# MCU.net
KiCad netlist of a schematic drawn in Altium Designer
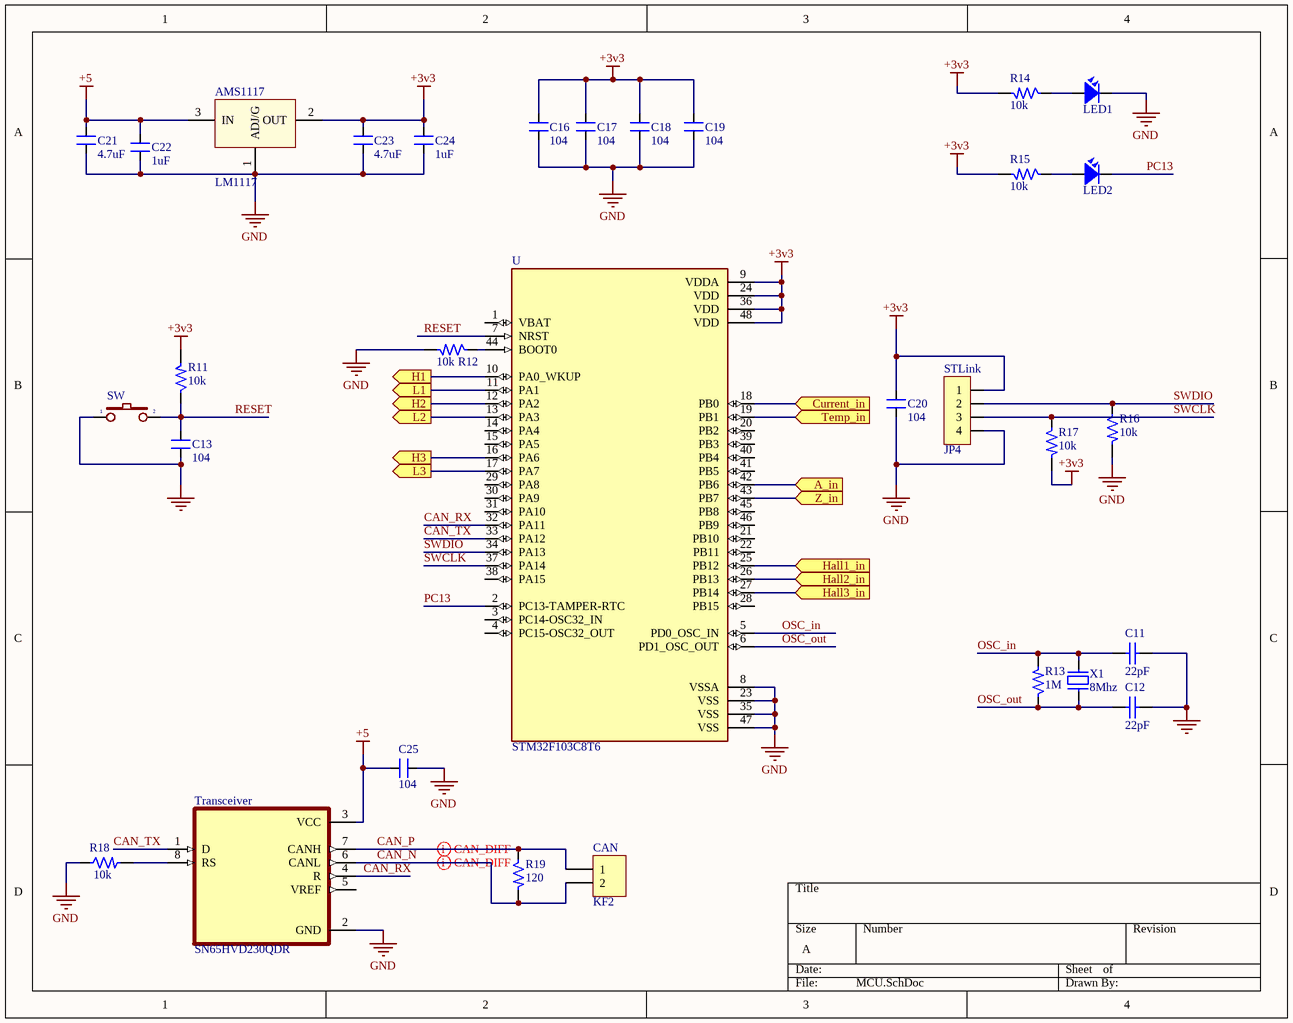
[diagram p0: MCU.SchDoc]

(export (version "E")
  (design (tool "Eeschema 10.0.6"))
  (components
    (comp (ref "AMS1117")
      (value "LM1117")
      (footprint "SOT223-4N")
      (description "Available in 1.8V, 2.5V, 2.85V, 3.3V, 5V, and  Adjustable Versions")
      (libsource (lib "echipkool-com-library") (part "LM1117"))
    )
    (comp (ref "C11")
      (value "22pF")
      (footprint "CAP FILM 0603_1608")
      (description "Capacitor")
      (fields (field (name "PUBLISHER") "Altium Limited"))
      (libsource (lib "My Library") (part "CapSMD"))
    )
    (comp (ref "C12")
      (value "22pF")
      (footprint "CAP FILM 0603_1608")
      (description "Capacitor")
      (fields (field (name "PUBLISHER") "Altium Limited"))
      (libsource (lib "My Library") (part "CapSMD"))
    )
    (comp (ref "C13")
      (value "104")
      (footprint "CAP FILM 0603_1608")
      (fields (field (name "DESIGNED BY") "VanDungEvn"))
      (libsource (lib "echipkool-com-library") (part "CN"))
    )
    (comp (ref "C16")
      (value "104")
      (footprint "CAP FILM 0603_1608")
      (fields (field (name "DESIGNED BY") "VanDungEvn"))
      (libsource (lib "echipkool-com-library") (part "CN"))
    )
    (comp (ref "C17")
      (value "104")
      (footprint "CAP FILM 0603_1608")
      (fields (field (name "DESIGNED BY") "VanDungEvn"))
      (libsource (lib "echipkool-com-library") (part "CN"))
    )
    (comp (ref "C18")
      (value "104")
      (footprint "CAP FILM 0603_1608")
      (fields (field (name "DESIGNED BY") "VanDungEvn"))
      (libsource (lib "echipkool-com-library") (part "CN"))
    )
    (comp (ref "C19")
      (value "104")
      (footprint "CAP FILM 0603_1608")
      (fields (field (name "DESIGNED BY") "VanDungEvn"))
      (libsource (lib "echipkool-com-library") (part "CN"))
    )
    (comp (ref "C20")
      (value "104")
      (footprint "CAP FILM 0603_1608")
      (fields (field (name "DESIGNED BY") "VanDungEvn"))
      (libsource (lib "echipkool-com-library") (part "CN"))
    )
    (comp (ref "C21")
      (value "4.7uF")
      (footprint "CAP FILM 0603_1608")
      (fields (field (name "DESIGNED BY") "VanDungEvn"))
      (libsource (lib "echipkool-com-library") (part "CN"))
    )
    (comp (ref "C22")
      (value "1uF")
      (footprint "CAP FILM 0603_1608")
      (fields (field (name "DESIGNED BY") "VanDungEvn"))
      (libsource (lib "echipkool-com-library") (part "CN"))
    )
    (comp (ref "C23")
      (value "4.7uF")
      (footprint "CAP FILM 0603_1608")
      (fields (field (name "DESIGNED BY") "VanDungEvn"))
      (libsource (lib "echipkool-com-library") (part "CN"))
    )
    (comp (ref "C24")
      (value "1uF")
      (footprint "CAP FILM 0603_1608")
      (fields (field (name "DESIGNED BY") "VanDungEvn"))
      (libsource (lib "echipkool-com-library") (part "CN"))
    )
    (comp (ref "C25")
      (value "104")
      (footprint "CAP FILM 0603_1608")
      (fields (field (name "DESIGNED BY") "VanDungEvn"))
      (libsource (lib "echipkool-com-library") (part "CN"))
    )
    (comp (ref "CAN")
      (value "KF2")
      (footprint "KF2-5.08")
      (fields
        (field (name "MANUFACTURER") "Würth Elektronik eiSos GmbH")
        (field (name "PARTNO") "691103110002")
        (field (name "CREATED BY") "Karrer Zheng")
      )
      (libsource (lib "LIBRARYALT") (part "KF2"))
    )
    (comp (ref "LED1")
      (value "LED SMD")
      (footprint "LED 0603_1608 GREEN")
      (libsource (lib "echipkool-com-library") (part "LED-SMD-0805"))
    )
    (comp (ref "LED2")
      (value "LED SMD")
      (footprint "LED 0603_1608 GREEN")
      (libsource (lib "echipkool-com-library") (part "LED-SMD-0805"))
    )
    (comp (ref "R11")
      (value "10k")
      (footprint "RES 0603_1608")
      (description "Resistor 1/4W")
      (libsource (lib "echipkool-com-library") (part "R"))
    )
    (comp (ref "R12")
      (value "10k")
      (footprint "RES 0603_1608")
      (description "Resistor 1/4W")
      (libsource (lib "echipkool-com-library") (part "R"))
    )
    (comp (ref "R13")
      (value "1M")
      (footprint "RES 0603_1608")
      (description "Resistor 1/4W")
      (libsource (lib "echipkool-com-library") (part "R"))
    )
    (comp (ref "R14")
      (value "10k")
      (footprint "RES 0603_1608")
      (description "Resistor 1/4W")
      (libsource (lib "echipkool-com-library") (part "R"))
    )
    (comp (ref "R15")
      (value "10k")
      (footprint "RES 0603_1608")
      (description "Resistor 1/4W")
      (libsource (lib "echipkool-com-library") (part "R"))
    )
    (comp (ref "R16")
      (value "10k")
      (footprint "RES 0603_1608")
      (description "Resistor 1/4W")
      (libsource (lib "echipkool-com-library") (part "R"))
    )
    (comp (ref "R17")
      (value "10k")
      (footprint "RES 0603_1608")
      (description "Resistor 1/4W")
      (libsource (lib "echipkool-com-library") (part "R"))
    )
    (comp (ref "R18")
      (value "10k")
      (footprint "RES 0603_1608")
      (description "Resistor 1/4W")
      (libsource (lib "echipkool-com-library") (part "R"))
    )
    (comp (ref "R19")
      (value "120")
      (footprint "RES 0603_1608")
      (description "Resistor 1/4W")
      (libsource (lib "echipkool-com-library") (part "R"))
    )
    (comp (ref "STLink")
      (value "JP4")
      (footprint "JP4-D1C")
      (description "WR-PHD 2.54 mm Angled Socket Header")
      (fields
        (field (name "MANUFACTURER") "Würth Elektronik eiSos GmbH")
        (field (name "PARTNO") "613004143121")
        (field (name "CREATED BY") "Karrer Zheng")
      )
      (libsource (lib "LIBRARYALT") (part "JP4"))
    )
    (comp (ref "SW")
      (value "~")
      (footprint "SW1-SMD")
      (description "Switch button 2 pin")
      (libsource (lib "LIBRARYALT") (part "SW2"))
    )
    (comp (ref "Transceiver")
      (value "SN65HVD230QDR")
      (footprint "SOIC127P599X175-8N")
      (description "3.3-V CAN Transceiver with Standby Mode 8-SOIC -40 to 125")
      (fields (field (name "MF") "Texas Instruments"))
      (libsource (lib "SN65HVD230QDR") (part "SN65HVD230QDR"))
    )
    (comp (ref "U")
      (value "STM32F103C8T6")
      (footprint "QFP50P900X900X160-48N")
      (description "ARMÂ® CortexÂ®-M3 STM32F1 Microcontroller IC 32-Bit 72MHz 64KB _64K x 8_ FLASH")
      (fields (field (name "MF") "STMicroelectronics"))
      (libsource (lib "STM32F103C8T6") (part "STM32F103C8T6"))
    )
    (comp (ref "X1")
      (value "8Mhz")
      (footprint "XTAL-RU49/4")
      (description "Crystal, 32.768 KHz, -40 to 85 degC, 3.2 x 1.5 x 0.9 mm SMD")
      (libsource (lib "LIBRARYALT") (part "XT2"))
    )
  )
  (nets
    (net (code "1") (name "+3v3") (class "Default")
      (node (ref "AMS1117") (pin "2") (pinfunction "OUT_2") (pintype "passive"))
      (node (ref "C16") (pin "1") (pinfunction "1_1") (pintype "passive"))
      (node (ref "C17") (pin "1") (pinfunction "1_1") (pintype "passive"))
      (node (ref "C18") (pin "1") (pinfunction "1_1") (pintype "passive"))
      (node (ref "C19") (pin "1") (pinfunction "1_1") (pintype "passive"))
      (node (ref "C20") (pin "1") (pinfunction "1_1") (pintype "passive"))
      (node (ref "C23") (pin "1") (pinfunction "1_1") (pintype "passive"))
      (node (ref "C24") (pin "1") (pinfunction "1_1") (pintype "passive"))
      (node (ref "R11") (pin "2") (pinfunction "2_2") (pintype "passive"))
      (node (ref "R14") (pin "2") (pinfunction "2_2") (pintype "passive"))
      (node (ref "R15") (pin "2") (pinfunction "2_2") (pintype "passive"))
      (node (ref "R17") (pin "2") (pinfunction "2_2") (pintype "passive"))
      (node (ref "STLink") (pin "1") (pinfunction "1_1") (pintype "passive"))
      (node (ref "U") (pin "24") (pinfunction "VDD_24") (pintype "power_in"))
      (node (ref "U") (pin "36") (pinfunction "VDD_36") (pintype "power_in"))
      (node (ref "U") (pin "48") (pinfunction "VDD_48") (pintype "power_in"))
      (node (ref "U") (pin "9") (pinfunction "VDDA_9") (pintype "power_in"))
    )
    (net (code "2") (name "+5") (class "Default")
      (node (ref "AMS1117") (pin "3") (pinfunction "IN_3") (pintype "passive"))
      (node (ref "C21") (pin "1") (pinfunction "1_1") (pintype "passive"))
      (node (ref "C22") (pin "1") (pinfunction "1_1") (pintype "passive"))
      (node (ref "C25") (pin "1") (pinfunction "1_1") (pintype "passive"))
      (node (ref "Transceiver") (pin "3") (pinfunction "VCC_3") (pintype "power_in"))
    )
    (net (code "3") (name "/A_in") (class "Default")
      (node (ref "U") (pin "42") (pinfunction "PB6_42") (pintype "bidirectional"))
    )
    (net (code "4") (name "/CAN_N") (class "Default")
      (node (ref "CAN") (pin "2") (pinfunction "2_2") (pintype "passive"))
      (node (ref "R19") (pin "2") (pinfunction "2_2") (pintype "passive"))
      (node (ref "Transceiver") (pin "6") (pinfunction "CANL_6") (pintype "output"))
    )
    (net (code "5") (name "/CAN_P") (class "Default")
      (node (ref "CAN") (pin "1") (pinfunction "1_1") (pintype "passive"))
      (node (ref "R19") (pin "1") (pinfunction "1_1") (pintype "passive"))
      (node (ref "Transceiver") (pin "7") (pinfunction "CANH_7") (pintype "output"))
    )
    (net (code "6") (name "/CAN_RX") (class "Default")
      (node (ref "Transceiver") (pin "4") (pinfunction "R_4") (pintype "output"))
      (node (ref "U") (pin "32") (pinfunction "PA11_32") (pintype "bidirectional"))
    )
    (net (code "7") (name "/CAN_TX") (class "Default")
      (node (ref "Transceiver") (pin "1") (pinfunction "D_1") (pintype "input"))
      (node (ref "U") (pin "33") (pinfunction "PA12_33") (pintype "bidirectional"))
    )
    (net (code "8") (name "/Current_in") (class "Default")
      (node (ref "U") (pin "18") (pinfunction "PB0_18") (pintype "bidirectional"))
    )
    (net (code "9") (name "/H1") (class "Default")
      (node (ref "U") (pin "10") (pinfunction "PA0_WKUP_10") (pintype "bidirectional"))
    )
    (net (code "10") (name "/H2") (class "Default")
      (node (ref "U") (pin "12") (pinfunction "PA2_12") (pintype "bidirectional"))
    )
    (net (code "11") (name "/H3") (class "Default")
      (node (ref "U") (pin "16") (pinfunction "PA6_16") (pintype "bidirectional"))
    )
    (net (code "12") (name "/Hall1_in") (class "Default")
      (node (ref "U") (pin "25") (pinfunction "PB12_25") (pintype "bidirectional"))
    )
    (net (code "13") (name "/Hall2_in") (class "Default")
      (node (ref "U") (pin "26") (pinfunction "PB13_26") (pintype "bidirectional"))
    )
    (net (code "14") (name "/Hall3_in") (class "Default")
      (node (ref "U") (pin "27") (pinfunction "PB14_27") (pintype "bidirectional"))
    )
    (net (code "15") (name "/L1") (class "Default")
      (node (ref "U") (pin "11") (pinfunction "PA1_11") (pintype "bidirectional"))
    )
    (net (code "16") (name "/L2") (class "Default")
      (node (ref "U") (pin "13") (pinfunction "PA3_13") (pintype "bidirectional"))
    )
    (net (code "17") (name "/L3") (class "Default")
      (node (ref "U") (pin "17") (pinfunction "PA7_17") (pintype "bidirectional"))
    )
    (net (code "18") (name "/OSC_in") (class "Default")
      (node (ref "C11") (pin "2") (pinfunction "2_2") (pintype "passive"))
      (node (ref "R13") (pin "2") (pinfunction "2_2") (pintype "passive"))
      (node (ref "U") (pin "5") (pinfunction "PD0_OSC_IN_5") (pintype "bidirectional"))
      (node (ref "X1") (pin "2") (pinfunction "2_2") (pintype "passive"))
    )
    (net (code "19") (name "/OSC_out") (class "Default")
      (node (ref "C12") (pin "2") (pinfunction "2_2") (pintype "passive"))
      (node (ref "R13") (pin "1") (pinfunction "1_1") (pintype "passive"))
      (node (ref "U") (pin "6") (pinfunction "PD1_OSC_OUT_6") (pintype "bidirectional"))
      (node (ref "X1") (pin "1") (pinfunction "1_1") (pintype "passive"))
    )
    (net (code "20") (name "/PC13") (class "Default")
      (node (ref "LED2") (pin "2") (pinfunction "2_2") (pintype "passive"))
      (node (ref "U") (pin "2") (pinfunction "PC13-TAMPER-RTC_2") (pintype "bidirectional"))
    )
    (net (code "21") (name "/RESET") (class "Default")
      (node (ref "C13") (pin "1") (pinfunction "1_1") (pintype "passive"))
      (node (ref "R11") (pin "1") (pinfunction "1_1") (pintype "passive"))
      (node (ref "SW") (pin "2") (pinfunction "2_2") (pintype "passive"))
      (node (ref "U") (pin "7") (pinfunction "NRST_7") (pintype "input"))
    )
    (net (code "22") (name "/SWCLK") (class "Default")
      (node (ref "R17") (pin "1") (pinfunction "1_1") (pintype "passive"))
      (node (ref "STLink") (pin "3") (pinfunction "3_3") (pintype "passive"))
      (node (ref "U") (pin "37") (pinfunction "PA14_37") (pintype "bidirectional"))
    )
    (net (code "23") (name "/SWDIO") (class "Default")
      (node (ref "R16") (pin "1") (pinfunction "1_1") (pintype "passive"))
      (node (ref "STLink") (pin "2") (pinfunction "2_2") (pintype "passive"))
      (node (ref "U") (pin "34") (pinfunction "PA13_34") (pintype "bidirectional"))
    )
    (net (code "24") (name "/Temp_in") (class "Default")
      (node (ref "U") (pin "19") (pinfunction "PB1_19") (pintype "bidirectional"))
    )
    (net (code "25") (name "/Z_in") (class "Default")
      (node (ref "U") (pin "43") (pinfunction "PB7_43") (pintype "bidirectional"))
    )
    (net (code "26") (name "GND") (class "Default")
      (node (ref "AMS1117") (pin "1") (pinfunction "ADJ/G_1") (pintype "passive"))
      (node (ref "C11") (pin "1") (pinfunction "1_1") (pintype "passive"))
      (node (ref "C12") (pin "1") (pinfunction "1_1") (pintype "passive"))
      (node (ref "C13") (pin "2") (pinfunction "2_2") (pintype "passive"))
      (node (ref "C16") (pin "2") (pinfunction "2_2") (pintype "passive"))
      (node (ref "C17") (pin "2") (pinfunction "2_2") (pintype "passive"))
      (node (ref "C18") (pin "2") (pinfunction "2_2") (pintype "passive"))
      (node (ref "C19") (pin "2") (pinfunction "2_2") (pintype "passive"))
      (node (ref "C20") (pin "2") (pinfunction "2_2") (pintype "passive"))
      (node (ref "C21") (pin "2") (pinfunction "2_2") (pintype "passive"))
      (node (ref "C22") (pin "2") (pinfunction "2_2") (pintype "passive"))
      (node (ref "C23") (pin "2") (pinfunction "2_2") (pintype "passive"))
      (node (ref "C24") (pin "2") (pinfunction "2_2") (pintype "passive"))
      (node (ref "C25") (pin "2") (pinfunction "2_2") (pintype "passive"))
      (node (ref "LED1") (pin "2") (pinfunction "2_2") (pintype "passive"))
      (node (ref "R12") (pin "2") (pinfunction "2_2") (pintype "passive"))
      (node (ref "R16") (pin "2") (pinfunction "2_2") (pintype "passive"))
      (node (ref "R18") (pin "1") (pinfunction "1_1") (pintype "passive"))
      (node (ref "STLink") (pin "4") (pinfunction "4_4") (pintype "passive"))
      (node (ref "SW") (pin "1") (pinfunction "1_1") (pintype "passive"))
      (node (ref "Transceiver") (pin "2") (pinfunction "GND_2") (pintype "power_in"))
      (node (ref "U") (pin "23") (pinfunction "VSS_23") (pintype "power_in"))
      (node (ref "U") (pin "35") (pinfunction "VSS_35") (pintype "power_in"))
      (node (ref "U") (pin "47") (pinfunction "VSS_47") (pintype "power_in"))
      (node (ref "U") (pin "8") (pinfunction "VSSA_8") (pintype "power_in"))
    )
    (net (code "27") (name "Net-(LED1-Pad1)") (class "Default")
      (node (ref "LED1") (pin "1") (pinfunction "1_1") (pintype "passive"))
      (node (ref "R14") (pin "1") (pinfunction "1_1") (pintype "passive"))
    )
    (net (code "28") (name "Net-(LED2-Pad1)") (class "Default")
      (node (ref "LED2") (pin "1") (pinfunction "1_1") (pintype "passive"))
      (node (ref "R15") (pin "1") (pinfunction "1_1") (pintype "passive"))
    )
    (net (code "29") (name "Net-(Transceiver-RS)") (class "Default")
      (node (ref "R18") (pin "2") (pinfunction "2_2") (pintype "passive"))
      (node (ref "Transceiver") (pin "8") (pinfunction "RS_8") (pintype "input"))
    )
    (net (code "30") (name "Net-(U-BOOT0)") (class "Default")
      (node (ref "R12") (pin "1") (pinfunction "1_1") (pintype "passive"))
      (node (ref "U") (pin "44") (pinfunction "BOOT0_44") (pintype "input"))
    )
    (net (code "31") (name "unconnected-(Transceiver-VREF-Pad5)") (class "Default")
      (node (ref "Transceiver") (pin "5") (pinfunction "VREF_5") (pintype "output"))
    )
    (net (code "32") (name "unconnected-(U-PA4-Pad14)") (class "Default")
      (node (ref "U") (pin "14") (pinfunction "PA4_14") (pintype "bidirectional"))
    )
    (net (code "33") (name "unconnected-(U-PA5-Pad15)") (class "Default")
      (node (ref "U") (pin "15") (pinfunction "PA5_15") (pintype "bidirectional"))
    )
    (net (code "34") (name "unconnected-(U-PA8-Pad29)") (class "Default")
      (node (ref "U") (pin "29") (pinfunction "PA8_29") (pintype "bidirectional"))
    )
    (net (code "35") (name "unconnected-(U-PA9-Pad30)") (class "Default")
      (node (ref "U") (pin "30") (pinfunction "PA9_30") (pintype "bidirectional"))
    )
    (net (code "36") (name "unconnected-(U-PA10-Pad31)") (class "Default")
      (node (ref "U") (pin "31") (pinfunction "PA10_31") (pintype "bidirectional"))
    )
    (net (code "37") (name "unconnected-(U-PA15-Pad38)") (class "Default")
      (node (ref "U") (pin "38") (pinfunction "PA15_38") (pintype "bidirectional"))
    )
    (net (code "38") (name "unconnected-(U-PB2-Pad20)") (class "Default")
      (node (ref "U") (pin "20") (pinfunction "PB2_20") (pintype "bidirectional"))
    )
    (net (code "39") (name "unconnected-(U-PB3-Pad39)") (class "Default")
      (node (ref "U") (pin "39") (pinfunction "PB3_39") (pintype "bidirectional"))
    )
    (net (code "40") (name "unconnected-(U-PB4-Pad40)") (class "Default")
      (node (ref "U") (pin "40") (pinfunction "PB4_40") (pintype "bidirectional"))
    )
    (net (code "41") (name "unconnected-(U-PB5-Pad41)") (class "Default")
      (node (ref "U") (pin "41") (pinfunction "PB5_41") (pintype "bidirectional"))
    )
    (net (code "42") (name "unconnected-(U-PB8-Pad45)") (class "Default")
      (node (ref "U") (pin "45") (pinfunction "PB8_45") (pintype "bidirectional"))
    )
    (net (code "43") (name "unconnected-(U-PB9-Pad46)") (class "Default")
      (node (ref "U") (pin "46") (pinfunction "PB9_46") (pintype "bidirectional"))
    )
    (net (code "44") (name "unconnected-(U-PB10-Pad21)") (class "Default")
      (node (ref "U") (pin "21") (pinfunction "PB10_21") (pintype "bidirectional"))
    )
    (net (code "45") (name "unconnected-(U-PB11-Pad22)") (class "Default")
      (node (ref "U") (pin "22") (pinfunction "PB11_22") (pintype "bidirectional"))
    )
    (net (code "46") (name "unconnected-(U-PB15-Pad28)") (class "Default")
      (node (ref "U") (pin "28") (pinfunction "PB15_28") (pintype "bidirectional"))
    )
    (net (code "47") (name "unconnected-(U-PC14-OSC32_IN-Pad3)") (class "Default")
      (node (ref "U") (pin "3") (pinfunction "PC14-OSC32_IN_3") (pintype "bidirectional"))
    )
    (net (code "48") (name "unconnected-(U-PC15-OSC32_OUT-Pad4)") (class "Default")
      (node (ref "U") (pin "4") (pinfunction "PC15-OSC32_OUT_4") (pintype "bidirectional"))
    )
    (net (code "49") (name "unconnected-(U-VBAT-Pad1)") (class "Default")
      (node (ref "U") (pin "1") (pinfunction "VBAT_1") (pintype "bidirectional"))
    )
  )
)
